# F200s.net
KiCad netlist of a schematic drawn in Altium Designer
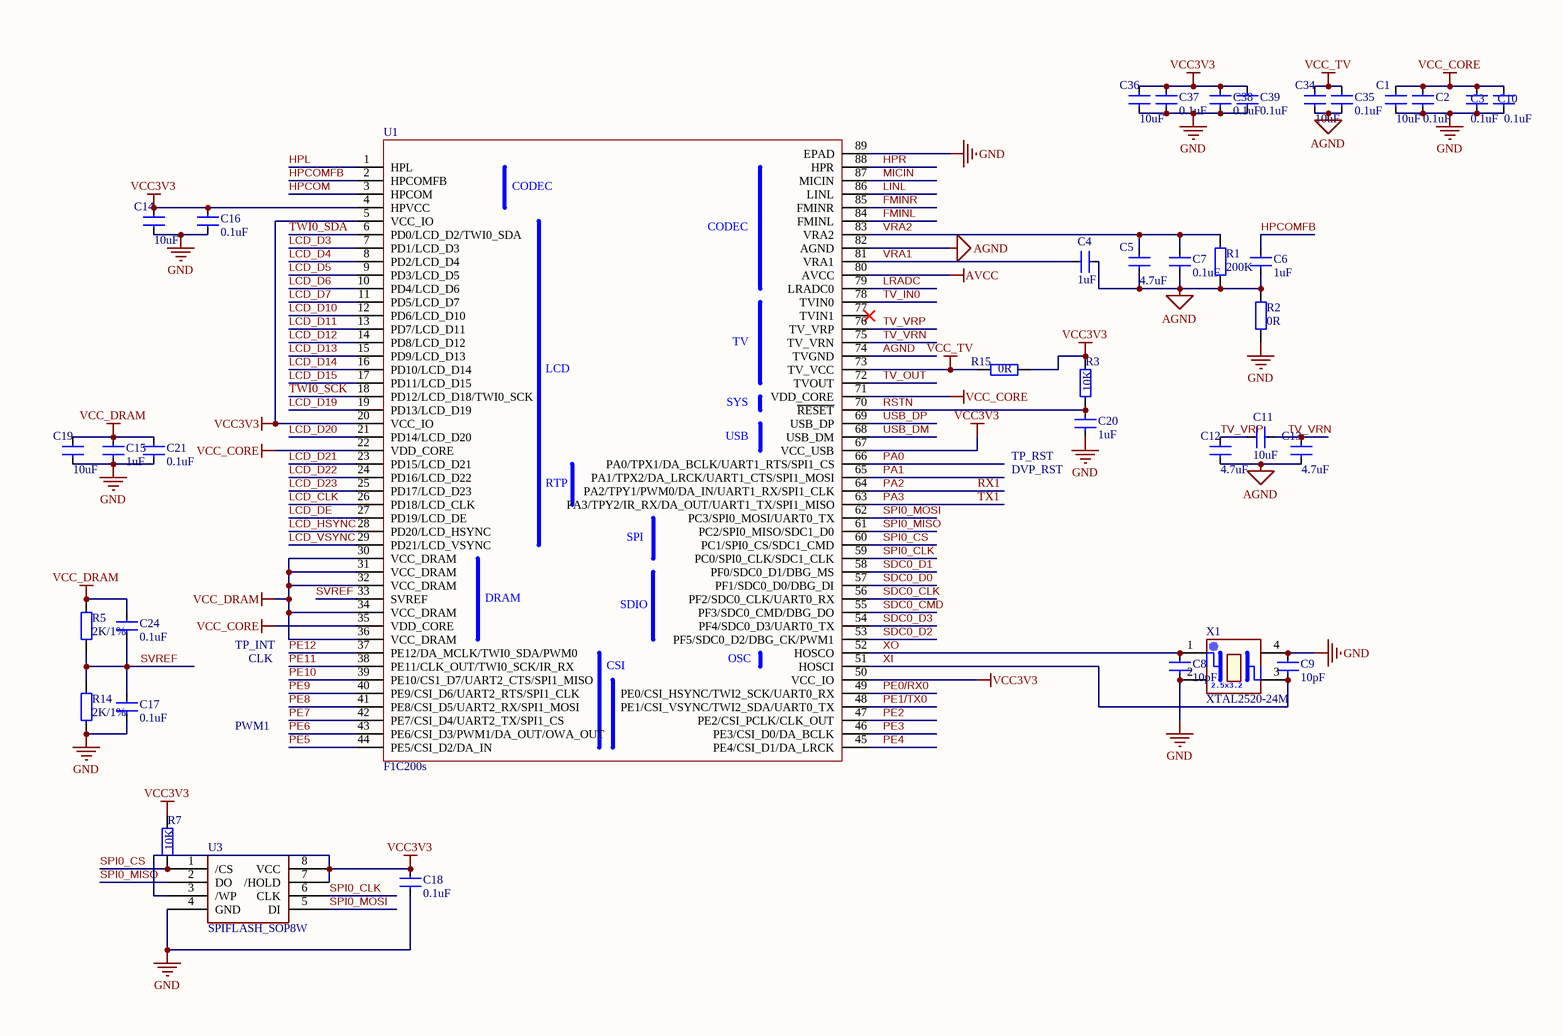
[diagram p0: F200s.SchDoc]

(export (version "E")
  (design (tool "Eeschema 10.0.6"))
  (components
    (comp (ref "C1")
      (value "10uF")
      (footprint "C0402")
      (description "普通小电容")
      (libsource (lib "LIB_MANGO") (part "CAP"))
    )
    (comp (ref "C2")
      (value "0.1uF")
      (footprint "C0402")
      (description "普通小电容")
      (libsource (lib "LIB_MANGO") (part "CAP"))
    )
    (comp (ref "C3")
      (value "0.1uF")
      (footprint "C0402")
      (description "普通小电容")
      (libsource (lib "LIB_MANGO") (part "CAP"))
    )
    (comp (ref "C4")
      (value "1uF")
      (footprint "C0402")
      (description "普通小电容")
      (libsource (lib "LIB_MANGO") (part "CAP"))
    )
    (comp (ref "C5")
      (value "4.7uF")
      (footprint "C0402")
      (description "普通小电容")
      (libsource (lib "LIB_MANGO") (part "CAP"))
    )
    (comp (ref "C6")
      (value "1uF")
      (footprint "C0402")
      (description "普通小电容")
      (libsource (lib "LIB_MANGO") (part "CAP"))
    )
    (comp (ref "C7")
      (value "0.1uF")
      (footprint "C0402")
      (description "普通小电容")
      (libsource (lib "LIB_MANGO") (part "CAP"))
    )
    (comp (ref "C8")
      (value "10pF")
      (footprint "C0402")
      (description "普通小电容")
      (libsource (lib "LIB_MANGO") (part "CAP"))
    )
    (comp (ref "C9")
      (value "10pF")
      (footprint "C0402")
      (description "普通小电容")
      (libsource (lib "LIB_MANGO") (part "CAP"))
    )
    (comp (ref "C10")
      (value "0.1uF")
      (footprint "C0402")
      (description "普通小电容")
      (libsource (lib "LIB_MANGO") (part "CAP"))
    )
    (comp (ref "C11")
      (value "10uF")
      (footprint "C0402")
      (description "普通小电容")
      (libsource (lib "LIB_MANGO") (part "CAP"))
    )
    (comp (ref "C12")
      (value "4.7uF")
      (footprint "C0402")
      (description "普通小电容")
      (libsource (lib "LIB_MANGO") (part "CAP"))
    )
    (comp (ref "C13")
      (value "4.7uF")
      (footprint "C0402")
      (description "普通小电容")
      (libsource (lib "LIB_MANGO") (part "CAP"))
    )
    (comp (ref "C14")
      (value "10uF")
      (footprint "C0402")
      (description "普通小电容")
      (libsource (lib "LIB_MANGO") (part "CAP"))
    )
    (comp (ref "C15")
      (value "1uF")
      (footprint "C0402")
      (description "普通小电容")
      (libsource (lib "LIB_MANGO") (part "CAP"))
    )
    (comp (ref "C16")
      (value "0.1uF")
      (footprint "C0402")
      (description "普通小电容")
      (libsource (lib "LIB_MANGO") (part "CAP"))
    )
    (comp (ref "C17")
      (value "0.1uF")
      (footprint "C0402")
      (description "普通小电容")
      (libsource (lib "LIB_MANGO") (part "CAP"))
    )
    (comp (ref "C18")
      (value "0.1uF")
      (footprint "C0402")
      (description "普通小电容")
      (libsource (lib "LIB_MANGO") (part "CAP"))
    )
    (comp (ref "C19")
      (value "10uF")
      (footprint "C0402")
      (description "普通小电容")
      (libsource (lib "LIB_MANGO") (part "CAP"))
    )
    (comp (ref "C20")
      (value "1uF")
      (footprint "C0402")
      (description "普通小电容")
      (libsource (lib "LIB_MANGO") (part "CAP"))
    )
    (comp (ref "C21")
      (value "0.1uF")
      (footprint "C0402")
      (description "普通小电容")
      (libsource (lib "LIB_MANGO") (part "CAP"))
    )
    (comp (ref "C24")
      (value "0.1uF")
      (footprint "C0402")
      (description "普通小电容")
      (libsource (lib "LIB_MANGO") (part "CAP"))
    )
    (comp (ref "C34")
      (value "10uF")
      (footprint "C0402")
      (description "普通小电容")
      (libsource (lib "LIB_MANGO") (part "CAP"))
    )
    (comp (ref "C35")
      (value "0.1uF")
      (footprint "C0402")
      (description "普通小电容")
      (libsource (lib "LIB_MANGO") (part "CAP"))
    )
    (comp (ref "C36")
      (value "10uF")
      (footprint "C0402")
      (description "普通小电容")
      (libsource (lib "LIB_MANGO") (part "CAP"))
    )
    (comp (ref "C37")
      (value "0.1uF")
      (footprint "C0402")
      (description "普通小电容")
      (libsource (lib "LIB_MANGO") (part "CAP"))
    )
    (comp (ref "C38")
      (value "0.1uF")
      (footprint "C0402")
      (description "普通小电容")
      (libsource (lib "LIB_MANGO") (part "CAP"))
    )
    (comp (ref "C39")
      (value "0.1uF")
      (footprint "C0402")
      (description "普通小电容")
      (libsource (lib "LIB_MANGO") (part "CAP"))
    )
    (comp (ref "R1")
      (value "200K")
      (footprint "R0402")
      (description "普通电阻")
      (libsource (lib "") (part "RES_1"))
    )
    (comp (ref "R2")
      (value "0R")
      (footprint "R0402")
      (description "普通电阻")
      (libsource (lib "") (part "RES_1"))
    )
    (comp (ref "R3")
      (value "10K")
      (footprint "R0402")
      (description "普通电阻")
      (libsource (lib "") (part "RES_1"))
    )
    (comp (ref "R5")
      (value "2K/1%")
      (footprint "R0402")
      (description "普通电阻")
      (libsource (lib "") (part "RES_1"))
    )
    (comp (ref "R7")
      (value "10K")
      (footprint "R0402")
      (description "普通电阻")
      (libsource (lib "") (part "RES_1"))
    )
    (comp (ref "R14")
      (value "2K/1%")
      (footprint "R0402")
      (description "普通电阻")
      (libsource (lib "") (part "RES_1"))
    )
    (comp (ref "R15")
      (value "0R")
      (footprint "R0402")
      (description "普通电阻")
      (libsource (lib "LIB_MANGO") (part "RES"))
    )
    (comp (ref "U1")
      (value "F1C200s")
      (footprint "QFN40P1000X1000X85_HS-89N")
      (libsource (lib "A") (part "F1C200s"))
    )
    (comp (ref "U3")
      (value "SPIFLASH_SOP8W")
      (footprint "WSON-SPIFLASH")
      (libsource (lib "LIB_MANGO") (part "SPIFLASH_SOP8W"))
    )
    (comp (ref "X1")
      (value "XTAL2520-24M")
      (footprint "XTAL2520")
      (libsource (lib "LIB_MANGO") (part "XTAL3225"))
    )
  )
  (nets
    (net (code "1") (name "/FMINL") (class "Default")
      (node (ref "U1") (pin "84") (pinfunction "FMINL_84") (pintype "passive"))
    )
    (net (code "2") (name "/FMINR") (class "Default")
      (node (ref "U1") (pin "85") (pinfunction "FMINR_85") (pintype "passive"))
    )
    (net (code "3") (name "/HPCOM") (class "Default")
      (node (ref "U1") (pin "3") (pinfunction "HPCOM_3") (pintype "passive"))
    )
    (net (code "4") (name "/HPCOMFB") (class "Default")
      (node (ref "C6") (pin "1") (pinfunction "1_1") (pintype "passive"))
      (node (ref "U1") (pin "2") (pinfunction "HPCOMFB_2") (pintype "passive"))
    )
    (net (code "5") (name "/HPL") (class "Default")
      (node (ref "U1") (pin "1") (pinfunction "HPL_1") (pintype "passive"))
    )
    (net (code "6") (name "/HPR") (class "Default")
      (node (ref "U1") (pin "88") (pinfunction "HPR_88") (pintype "passive"))
    )
    (net (code "7") (name "/LCD_CLK") (class "Default")
      (node (ref "U1") (pin "26") (pinfunction "PD18/LCD_CLK_26") (pintype "passive"))
    )
    (net (code "8") (name "/LCD_D3") (class "Default")
      (node (ref "U1") (pin "7") (pinfunction "PD1/LCD_D3_7") (pintype "passive"))
    )
    (net (code "9") (name "/LCD_D4") (class "Default")
      (node (ref "U1") (pin "8") (pinfunction "PD2/LCD_D4_8") (pintype "passive"))
    )
    (net (code "10") (name "/LCD_D5") (class "Default")
      (node (ref "U1") (pin "9") (pinfunction "PD3/LCD_D5_9") (pintype "passive"))
    )
    (net (code "11") (name "/LCD_D6") (class "Default")
      (node (ref "U1") (pin "10") (pinfunction "PD4/LCD_D6_10") (pintype "passive"))
    )
    (net (code "12") (name "/LCD_D7") (class "Default")
      (node (ref "U1") (pin "11") (pinfunction "PD5/LCD_D7_11") (pintype "passive"))
    )
    (net (code "13") (name "/LCD_D10") (class "Default")
      (node (ref "U1") (pin "12") (pinfunction "PD6/LCD_D10_12") (pintype "passive"))
    )
    (net (code "14") (name "/LCD_D11") (class "Default")
      (node (ref "U1") (pin "13") (pinfunction "PD7/LCD_D11_13") (pintype "passive"))
    )
    (net (code "15") (name "/LCD_D12") (class "Default")
      (node (ref "U1") (pin "14") (pinfunction "PD8/LCD_D12_14") (pintype "passive"))
    )
    (net (code "16") (name "/LCD_D13") (class "Default")
      (node (ref "U1") (pin "15") (pinfunction "PD9/LCD_D13_15") (pintype "passive"))
    )
    (net (code "17") (name "/LCD_D14") (class "Default")
      (node (ref "U1") (pin "16") (pinfunction "PD10/LCD_D14_16") (pintype "passive"))
    )
    (net (code "18") (name "/LCD_D15") (class "Default")
      (node (ref "U1") (pin "17") (pinfunction "PD11/LCD_D15_17") (pintype "passive"))
    )
    (net (code "19") (name "/LCD_D19") (class "Default")
      (node (ref "U1") (pin "19") (pinfunction "PD13/LCD_D19_19") (pintype "passive"))
    )
    (net (code "20") (name "/LCD_D20") (class "Default")
      (node (ref "U1") (pin "21") (pinfunction "PD14/LCD_D20_21") (pintype "passive"))
    )
    (net (code "21") (name "/LCD_D21") (class "Default")
      (node (ref "U1") (pin "23") (pinfunction "PD15/LCD_D21_23") (pintype "passive"))
    )
    (net (code "22") (name "/LCD_D22") (class "Default")
      (node (ref "U1") (pin "24") (pinfunction "PD16/LCD_D22_24") (pintype "passive"))
    )
    (net (code "23") (name "/LCD_D23") (class "Default")
      (node (ref "U1") (pin "25") (pinfunction "PD17/LCD_D23_25") (pintype "passive"))
    )
    (net (code "24") (name "/LCD_DE") (class "Default")
      (node (ref "U1") (pin "27") (pinfunction "PD19/LCD_DE_27") (pintype "passive"))
    )
    (net (code "25") (name "/LCD_HSYNC") (class "Default")
      (node (ref "U1") (pin "28") (pinfunction "PD20/LCD_HSYNC_28") (pintype "passive"))
    )
    (net (code "26") (name "/LCD_VSYNC") (class "Default")
      (node (ref "U1") (pin "29") (pinfunction "PD21/LCD_VSYNC_29") (pintype "passive"))
    )
    (net (code "27") (name "/LINL") (class "Default")
      (node (ref "U1") (pin "86") (pinfunction "LINL_86") (pintype "passive"))
    )
    (net (code "28") (name "/LRADC") (class "Default")
      (node (ref "U1") (pin "79") (pinfunction "LRADC0_79") (pintype "passive"))
    )
    (net (code "29") (name "/MICIN") (class "Default")
      (node (ref "U1") (pin "87") (pinfunction "MICIN_87") (pintype "passive"))
    )
    (net (code "30") (name "/PA0") (class "Default")
      (node (ref "U1") (pin "66") (pinfunction "PA0/TPX1/DA_BCLK/UART1_RTS/SPI1_CS_66") (pintype "passive"))
    )
    (net (code "31") (name "/PA1") (class "Default")
      (node (ref "U1") (pin "65") (pinfunction "PA1/TPX2/DA_LRCK/UART1_CTS/SPI1_MOSI_65") (pintype "passive"))
    )
    (net (code "32") (name "/PA2") (class "Default")
      (node (ref "U1") (pin "64") (pinfunction "PA2/TPY1/PWM0/DA_IN/UART1_RX/SPI1_CLK_64") (pintype "passive"))
    )
    (net (code "33") (name "/PA3") (class "Default")
      (node (ref "U1") (pin "63") (pinfunction "PA3/TPY2/IR_RX/DA_OUT/UART1_TX/SPI1_MISO_63") (pintype "passive"))
    )
    (net (code "34") (name "/PE0{slash}RX0") (class "Default")
      (node (ref "U1") (pin "49") (pinfunction "PE0/CSI_HSYNC/TWI2_SCK/UART0_RX_49") (pintype "passive"))
    )
    (net (code "35") (name "/PE1{slash}TX0") (class "Default")
      (node (ref "U1") (pin "48") (pinfunction "PE1/CSI_VSYNC/TWI2_SDA/UART0_TX_48") (pintype "passive"))
    )
    (net (code "36") (name "/PE2") (class "Default")
      (node (ref "U1") (pin "47") (pinfunction "PE2/CSI_PCLK/CLK_OUT_47") (pintype "passive"))
    )
    (net (code "37") (name "/PE3") (class "Default")
      (node (ref "U1") (pin "46") (pinfunction "PE3/CSI_D0/DA_BCLK_46") (pintype "passive"))
    )
    (net (code "38") (name "/PE4") (class "Default")
      (node (ref "U1") (pin "45") (pinfunction "PE4/CSI_D1/DA_LRCK_45") (pintype "passive"))
    )
    (net (code "39") (name "/PE5") (class "Default")
      (node (ref "U1") (pin "44") (pinfunction "PE5/CSI_D2/DA_IN_44") (pintype "passive"))
    )
    (net (code "40") (name "/PE6") (class "Default")
      (node (ref "U1") (pin "43") (pinfunction "PE6/CSI_D3/PWM1/DA_OUT/OWA_OUT_43") (pintype "passive"))
    )
    (net (code "41") (name "/PE7") (class "Default")
      (node (ref "U1") (pin "42") (pinfunction "PE7/CSI_D4/UART2_TX/SPI1_CS_42") (pintype "passive"))
    )
    (net (code "42") (name "/PE8") (class "Default")
      (node (ref "U1") (pin "41") (pinfunction "PE8/CSI_D5/UART2_RX/SPI1_MOSI_41") (pintype "passive"))
    )
    (net (code "43") (name "/PE9") (class "Default")
      (node (ref "U1") (pin "40") (pinfunction "PE9/CSI_D6/UART2_RTS/SPI1_CLK_40") (pintype "passive"))
    )
    (net (code "44") (name "/PE10") (class "Default")
      (node (ref "U1") (pin "39") (pinfunction "PE10/CS1_D7/UART2_CTS/SPI1_MISO_39") (pintype "passive"))
    )
    (net (code "45") (name "/PE11") (class "Default")
      (node (ref "U1") (pin "38") (pinfunction "PE11/CLK_OUT/TWI0_SCK/IR_RX_38") (pintype "passive"))
    )
    (net (code "46") (name "/PE12") (class "Default")
      (node (ref "U1") (pin "37") (pinfunction "PE12/DA_MCLK/TWI0_SDA/PWM0_37") (pintype "passive"))
    )
    (net (code "47") (name "/RSTN") (class "Default")
      (node (ref "C20") (pin "1") (pinfunction "1_1") (pintype "passive"))
      (node (ref "R3") (pin "1") (pinfunction "1_1") (pintype "passive"))
      (node (ref "U1") (pin "70") (pinfunction "~{RESET}_70") (pintype "passive"))
    )
    (net (code "48") (name "/SDC0_CLK") (class "Default")
      (node (ref "U1") (pin "56") (pinfunction "PF2/SDC0_CLK/UART0_RX_56") (pintype "passive"))
    )
    (net (code "49") (name "/SDC0_CMD") (class "Default")
      (node (ref "U1") (pin "55") (pinfunction "PF3/SDC0_CMD/DBG_DO_55") (pintype "passive"))
    )
    (net (code "50") (name "/SDC0_D0") (class "Default")
      (node (ref "U1") (pin "57") (pinfunction "PF1/SDC0_D0/DBG_DI_57") (pintype "passive"))
    )
    (net (code "51") (name "/SDC0_D1") (class "Default")
      (node (ref "U1") (pin "58") (pinfunction "PF0/SDC0_D1/DBG_MS_58") (pintype "passive"))
    )
    (net (code "52") (name "/SDC0_D2") (class "Default")
      (node (ref "U1") (pin "53") (pinfunction "PF5/SDC0_D2/DBG_CK/PWM1_53") (pintype "passive"))
    )
    (net (code "53") (name "/SDC0_D3") (class "Default")
      (node (ref "U1") (pin "54") (pinfunction "PF4/SDC0_D3/UART0_TX_54") (pintype "passive"))
    )
    (net (code "54") (name "/SPI0_CLK") (class "Default")
      (node (ref "U1") (pin "59") (pinfunction "PC0/SPI0_CLK/SDC1_CLK_59") (pintype "passive"))
      (node (ref "U3") (pin "6") (pinfunction "CLK_6") (pintype "passive"))
    )
    (net (code "55") (name "/SPI0_CS") (class "Default")
      (node (ref "R7") (pin "1") (pinfunction "1_1") (pintype "passive"))
      (node (ref "U1") (pin "60") (pinfunction "PC1/SPI0_CS/SDC1_CMD_60") (pintype "passive"))
      (node (ref "U3") (pin "1") (pinfunction "/CS_1") (pintype "passive"))
    )
    (net (code "56") (name "/SPI0_MISO") (class "Default")
      (node (ref "U1") (pin "61") (pinfunction "PC2/SPI0_MISO/SDC1_D0_61") (pintype "passive"))
      (node (ref "U3") (pin "2") (pinfunction "DO_2") (pintype "passive"))
    )
    (net (code "57") (name "/SPI0_MOSI") (class "Default")
      (node (ref "U1") (pin "62") (pinfunction "PC3/SPI0_MOSI/UART0_TX_62") (pintype "passive"))
      (node (ref "U3") (pin "5") (pinfunction "DI_5") (pintype "passive"))
    )
    (net (code "58") (name "/SVREF") (class "Default")
      (node (ref "C17") (pin "2") (pinfunction "2_2") (pintype "passive"))
      (node (ref "C24") (pin "1") (pinfunction "1_1") (pintype "passive"))
      (node (ref "R14") (pin "2") (pinfunction "2_2") (pintype "passive"))
      (node (ref "R5") (pin "1") (pinfunction "1_1") (pintype "passive"))
      (node (ref "U1") (pin "33") (pinfunction "SVREF_33") (pintype "passive"))
    )
    (net (code "59") (name "/TV_IN0") (class "Default")
      (node (ref "U1") (pin "78") (pinfunction "TVIN0_78") (pintype "passive"))
    )
    (net (code "60") (name "/TV_OUT") (class "Default")
      (node (ref "U1") (pin "72") (pinfunction "TVOUT_72") (pintype "passive"))
    )
    (net (code "61") (name "/TV_VRN") (class "Default")
      (node (ref "C11") (pin "1") (pinfunction "1_1") (pintype "passive"))
      (node (ref "C13") (pin "2") (pinfunction "2_2") (pintype "passive"))
      (node (ref "U1") (pin "75") (pinfunction "TV_VRN_75") (pintype "passive"))
    )
    (net (code "62") (name "/TV_VRP") (class "Default")
      (node (ref "C11") (pin "2") (pinfunction "2_2") (pintype "passive"))
      (node (ref "C12") (pin "2") (pinfunction "2_2") (pintype "passive"))
      (node (ref "U1") (pin "76") (pinfunction "TV_VRP_76") (pintype "passive"))
    )
    (net (code "63") (name "/TWI0_SCK") (class "Default")
      (node (ref "U1") (pin "18") (pinfunction "PD12/LCD_D18/TWI0_SCK_18") (pintype "passive"))
    )
    (net (code "64") (name "/TWI0_SDA") (class "Default")
      (node (ref "U1") (pin "6") (pinfunction "PD0/LCD_D2/TWI0_SDA_6") (pintype "passive"))
    )
    (net (code "65") (name "/USB_DM") (class "Default")
      (node (ref "U1") (pin "68") (pinfunction "USB_DM_68") (pintype "passive"))
    )
    (net (code "66") (name "/USB_DP") (class "Default")
      (node (ref "U1") (pin "69") (pinfunction "USB_DP_69") (pintype "passive"))
    )
    (net (code "67") (name "/VRA1") (class "Default")
      (node (ref "C4") (pin "1") (pinfunction "1_1") (pintype "passive"))
      (node (ref "U1") (pin "81") (pinfunction "VRA1_81") (pintype "passive"))
    )
    (net (code "68") (name "/VRA2") (class "Default")
      (node (ref "C5") (pin "2") (pinfunction "2_2") (pintype "passive"))
      (node (ref "C7") (pin "2") (pinfunction "2_2") (pintype "passive"))
      (node (ref "R1") (pin "2") (pinfunction "2_2") (pintype "passive"))
      (node (ref "U1") (pin "83") (pinfunction "VRA2_83") (pintype "passive"))
    )
    (net (code "69") (name "/XI") (class "Default")
      (node (ref "C9") (pin "1") (pinfunction "1_1") (pintype "passive"))
      (node (ref "U1") (pin "51") (pinfunction "HOSCI_51") (pintype "passive"))
      (node (ref "X1") (pin "3") (pinfunction "X2_3") (pintype "passive"))
    )
    (net (code "70") (name "/XO") (class "Default")
      (node (ref "C8") (pin "2") (pinfunction "2_2") (pintype "passive"))
      (node (ref "U1") (pin "52") (pinfunction "HOSCO_52") (pintype "passive"))
      (node (ref "X1") (pin "1") (pinfunction "X1_1") (pintype "passive"))
    )
    (net (code "71") (name "AGND") (class "Default")
      (node (ref "C12") (pin "1") (pinfunction "1_1") (pintype "passive"))
      (node (ref "C13") (pin "1") (pinfunction "1_1") (pintype "passive"))
      (node (ref "C34") (pin "1") (pinfunction "1_1") (pintype "passive"))
      (node (ref "C35") (pin "1") (pinfunction "1_1") (pintype "passive"))
      (node (ref "C4") (pin "2") (pinfunction "2_2") (pintype "passive"))
      (node (ref "C5") (pin "1") (pinfunction "1_1") (pintype "passive"))
      (node (ref "C6") (pin "2") (pinfunction "2_2") (pintype "passive"))
      (node (ref "C7") (pin "1") (pinfunction "1_1") (pintype "passive"))
      (node (ref "R1") (pin "1") (pinfunction "1_1") (pintype "passive"))
      (node (ref "R2") (pin "2") (pinfunction "2_2") (pintype "passive"))
      (node (ref "U1") (pin "74") (pinfunction "TVGND_74") (pintype "passive"))
      (node (ref "U1") (pin "82") (pinfunction "AGND_82") (pintype "passive"))
    )
    (net (code "72") (name "AVCC") (class "Default")
      (node (ref "U1") (pin "80") (pinfunction "AVCC_80") (pintype "passive"))
    )
    (net (code "73") (name "GND") (class "Default")
      (node (ref "C1") (pin "1") (pinfunction "1_1") (pintype "passive"))
      (node (ref "C10") (pin "1") (pinfunction "1_1") (pintype "passive"))
      (node (ref "C14") (pin "1") (pinfunction "1_1") (pintype "passive"))
      (node (ref "C15") (pin "1") (pinfunction "1_1") (pintype "passive"))
      (node (ref "C16") (pin "1") (pinfunction "1_1") (pintype "passive"))
      (node (ref "C17") (pin "1") (pinfunction "1_1") (pintype "passive"))
      (node (ref "C18") (pin "1") (pinfunction "1_1") (pintype "passive"))
      (node (ref "C19") (pin "1") (pinfunction "1_1") (pintype "passive"))
      (node (ref "C2") (pin "1") (pinfunction "1_1") (pintype "passive"))
      (node (ref "C20") (pin "2") (pinfunction "2_2") (pintype "passive"))
      (node (ref "C21") (pin "1") (pinfunction "1_1") (pintype "passive"))
      (node (ref "C3") (pin "1") (pinfunction "1_1") (pintype "passive"))
      (node (ref "C36") (pin "1") (pinfunction "1_1") (pintype "passive"))
      (node (ref "C37") (pin "1") (pinfunction "1_1") (pintype "passive"))
      (node (ref "C38") (pin "1") (pinfunction "1_1") (pintype "passive"))
      (node (ref "C39") (pin "1") (pinfunction "1_1") (pintype "passive"))
      (node (ref "C8") (pin "1") (pinfunction "1_1") (pintype "passive"))
      (node (ref "C9") (pin "2") (pinfunction "2_2") (pintype "passive"))
      (node (ref "R14") (pin "1") (pinfunction "1_1") (pintype "passive"))
      (node (ref "R2") (pin "1") (pinfunction "1_1") (pintype "passive"))
      (node (ref "U1") (pin "89") (pinfunction "EPAD_89") (pintype "passive"))
      (node (ref "U3") (pin "4") (pinfunction "GND_4") (pintype "passive"))
      (node (ref "X1") (pin "2") (pinfunction "NC1_2") (pintype "passive"))
      (node (ref "X1") (pin "4") (pinfunction "NC2_4") (pintype "passive"))
    )
    (net (code "74") (name "VCC3V3") (class "Default")
      (node (ref "C14") (pin "2") (pinfunction "2_2") (pintype "passive"))
      (node (ref "C16") (pin "2") (pinfunction "2_2") (pintype "passive"))
      (node (ref "C18") (pin "2") (pinfunction "2_2") (pintype "passive"))
      (node (ref "C36") (pin "2") (pinfunction "2_2") (pintype "passive"))
      (node (ref "C37") (pin "2") (pinfunction "2_2") (pintype "passive"))
      (node (ref "C38") (pin "2") (pinfunction "2_2") (pintype "passive"))
      (node (ref "C39") (pin "2") (pinfunction "2_2") (pintype "passive"))
      (node (ref "R15") (pin "1") (pinfunction "1_1") (pintype "passive"))
      (node (ref "R3") (pin "2") (pinfunction "2_2") (pintype "passive"))
      (node (ref "R7") (pin "2") (pinfunction "2_2") (pintype "passive"))
      (node (ref "U1") (pin "20") (pinfunction "VCC_IO_20") (pintype "passive"))
      (node (ref "U1") (pin "4") (pinfunction "HPVCC_4") (pintype "passive"))
      (node (ref "U1") (pin "5") (pinfunction "VCC_IO_5") (pintype "passive"))
      (node (ref "U1") (pin "50") (pinfunction "VCC_IO_50") (pintype "passive"))
      (node (ref "U1") (pin "67") (pinfunction "VCC_USB_67") (pintype "passive"))
      (node (ref "U3") (pin "3") (pinfunction "/WP_3") (pintype "passive"))
      (node (ref "U3") (pin "7") (pinfunction "/HOLD_7") (pintype "passive"))
      (node (ref "U3") (pin "8") (pinfunction "VCC_8") (pintype "passive"))
    )
    (net (code "75") (name "VCC_CORE") (class "Default")
      (node (ref "C1") (pin "2") (pinfunction "2_2") (pintype "passive"))
      (node (ref "C10") (pin "2") (pinfunction "2_2") (pintype "passive"))
      (node (ref "C2") (pin "2") (pinfunction "2_2") (pintype "passive"))
      (node (ref "C3") (pin "2") (pinfunction "2_2") (pintype "passive"))
      (node (ref "U1") (pin "22") (pinfunction "VDD_CORE_22") (pintype "passive"))
      (node (ref "U1") (pin "35") (pinfunction "VDD_CORE_35") (pintype "passive"))
      (node (ref "U1") (pin "71") (pinfunction "VDD_CORE_71") (pintype "passive"))
    )
    (net (code "76") (name "VCC_DRAM") (class "Default")
      (node (ref "C15") (pin "2") (pinfunction "2_2") (pintype "passive"))
      (node (ref "C19") (pin "2") (pinfunction "2_2") (pintype "passive"))
      (node (ref "C21") (pin "2") (pinfunction "2_2") (pintype "passive"))
      (node (ref "C24") (pin "2") (pinfunction "2_2") (pintype "passive"))
      (node (ref "R5") (pin "2") (pinfunction "2_2") (pintype "passive"))
      (node (ref "U1") (pin "30") (pinfunction "VCC_DRAM_30") (pintype "passive"))
      (node (ref "U1") (pin "31") (pinfunction "VCC_DRAM_31") (pintype "passive"))
      (node (ref "U1") (pin "32") (pinfunction "VCC_DRAM_32") (pintype "passive"))
      (node (ref "U1") (pin "34") (pinfunction "VCC_DRAM_34") (pintype "passive"))
      (node (ref "U1") (pin "36") (pinfunction "VCC_DRAM_36") (pintype "passive"))
    )
    (net (code "77") (name "VCC_TV") (class "Default")
      (node (ref "C34") (pin "2") (pinfunction "2_2") (pintype "passive"))
      (node (ref "C35") (pin "2") (pinfunction "2_2") (pintype "passive"))
      (node (ref "R15") (pin "2") (pinfunction "2_2") (pintype "passive"))
      (node (ref "U1") (pin "73") (pinfunction "TV_VCC_73") (pintype "passive"))
    )
    (net (code "78") (name "unconnected-(U1-TVIN1-Pad77)") (class "Default")
      (node (ref "U1") (pin "77") (pinfunction "TVIN1_77") (pintype "passive+no_connect"))
    )
  )
)
